# CPU_GPIO.net
KiCad netlist of a schematic drawn in Altium Designer
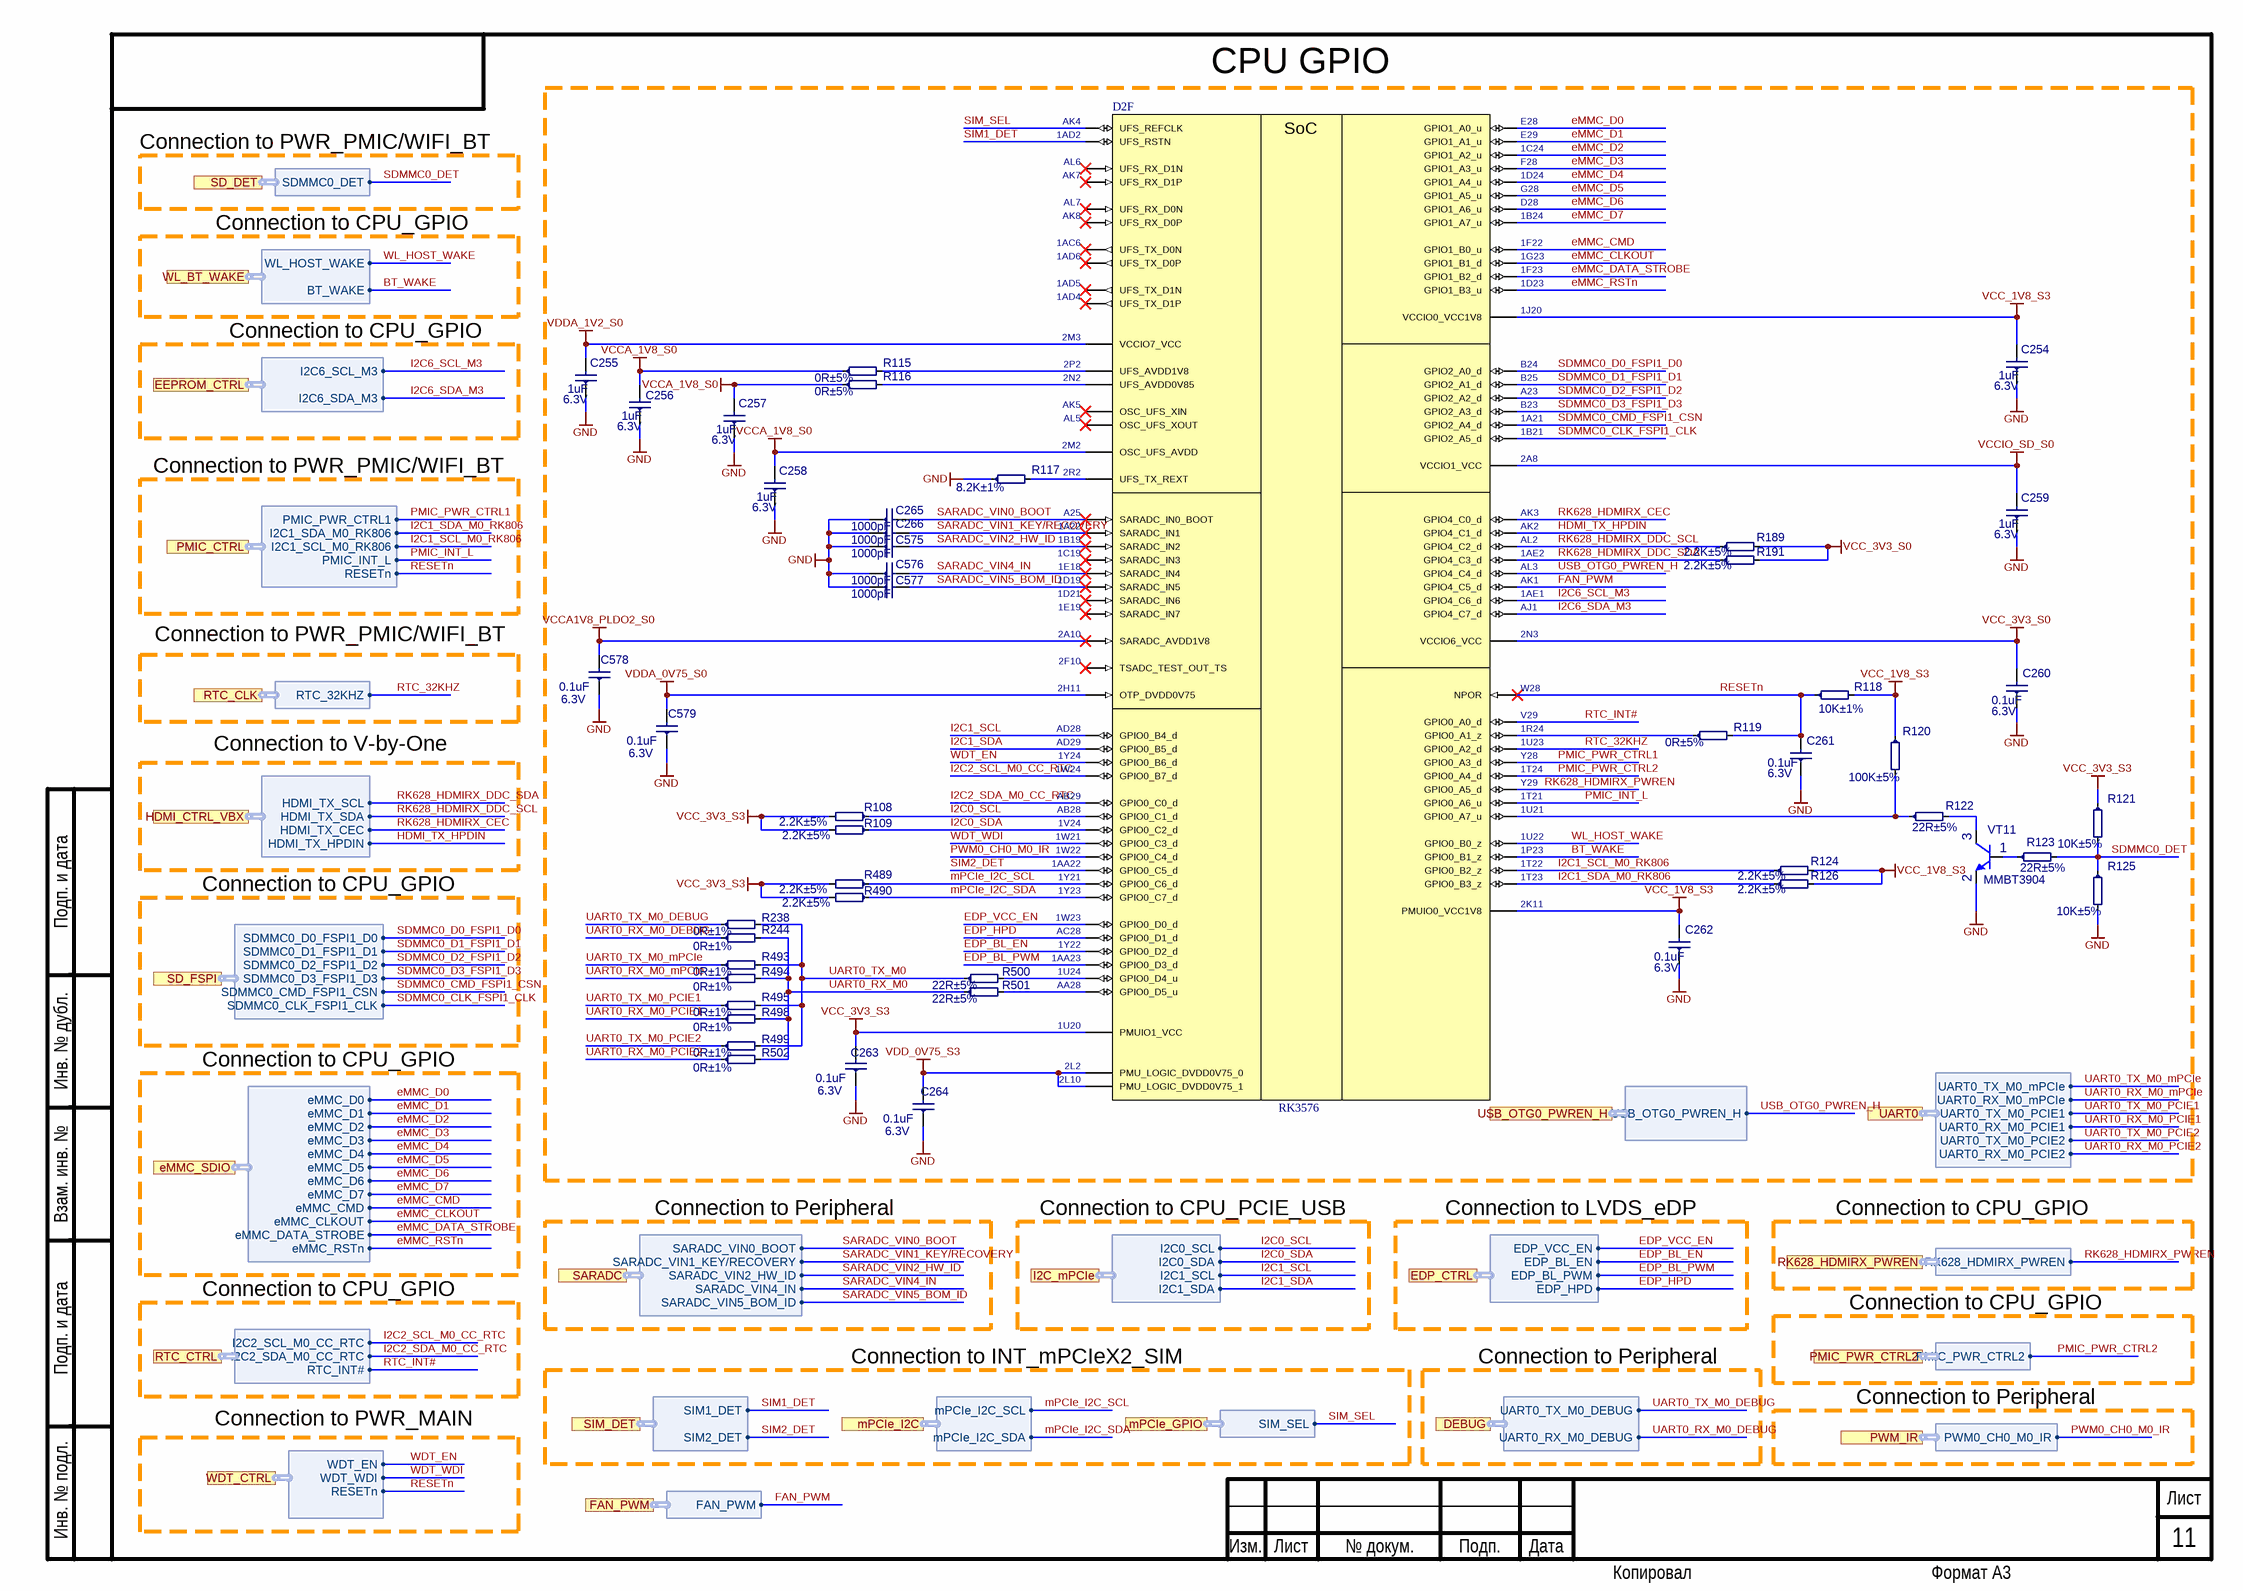
[diagram p0: CPU_GPIO.SchDoc]

(export (version "E")
  (design (tool "Eeschema 10.0.6"))
  (components
    (comp (ref "C254")
      (value "1uF")
      (footprint "C0201")
      (fields
        (field (name "VOLTAGE") "6.3V")
        (field (name "PART NUMBER") "0201-X5R-6.3V-1uF±20%")
        (field (name "TOLERANCE") "20%")
        (field (name "MANUFACTURER") "Murata Electronics")
      )
      (libsource (lib "ATB") (part "C"))
    )
    (comp (ref "C255")
      (value "1uF")
      (footprint "C0201")
      (fields
        (field (name "VOLTAGE") "6.3V")
        (field (name "PART NUMBER") "0201-X5R-6.3V-1uF±20%")
        (field (name "TOLERANCE") "20%")
        (field (name "MANUFACTURER") "Murata Electronics")
      )
      (libsource (lib "ATB") (part "C"))
    )
    (comp (ref "C256")
      (value "1uF")
      (footprint "C0201")
      (fields
        (field (name "VOLTAGE") "6.3V")
        (field (name "PART NUMBER") "0201-X5R-6.3V-1uF±20%")
        (field (name "TOLERANCE") "20%")
        (field (name "MANUFACTURER") "Murata Electronics")
      )
      (libsource (lib "ATB") (part "C"))
    )
    (comp (ref "C257")
      (value "1uF")
      (footprint "C0201")
      (fields
        (field (name "VOLTAGE") "6.3V")
        (field (name "PART NUMBER") "0201-X5R-6.3V-1uF±20%")
        (field (name "TOLERANCE") "20%")
        (field (name "MANUFACTURER") "Murata Electronics")
      )
      (libsource (lib "ATB") (part "C"))
    )
    (comp (ref "C258")
      (value "1uF")
      (footprint "C0201")
      (fields
        (field (name "VOLTAGE") "6.3V")
        (field (name "PART NUMBER") "0201-X5R-6.3V-1uF±20%")
        (field (name "TOLERANCE") "20%")
        (field (name "MANUFACTURER") "Murata Electronics")
      )
      (libsource (lib "ATB") (part "C"))
    )
    (comp (ref "C259")
      (value "1uF")
      (footprint "C0201")
      (fields
        (field (name "VOLTAGE") "6.3V")
        (field (name "PART NUMBER") "0201-X5R-6.3V-1uF±20%")
        (field (name "TOLERANCE") "20%")
        (field (name "MANUFACTURER") "Murata Electronics")
      )
      (libsource (lib "ATB") (part "C"))
    )
    (comp (ref "C260")
      (value "0.1uF")
      (footprint "C0201")
      (fields
        (field (name "VOLTAGE") "6.3V")
        (field (name "PART NUMBER") "0201-X5R-6.3V-0.1uF±10%")
        (field (name "TOLERANCE") "10%")
        (field (name "MANUFACTURER") "Yageo")
      )
      (libsource (lib "ATB") (part "C"))
    )
    (comp (ref "C261")
      (value "0.1uF")
      (footprint "C0201")
      (fields
        (field (name "VOLTAGE") "6.3V")
        (field (name "PART NUMBER") "0201-X5R-6.3V-0.1uF±10%")
        (field (name "TOLERANCE") "10%")
        (field (name "MANUFACTURER") "Yageo")
      )
      (libsource (lib "ATB") (part "C"))
    )
    (comp (ref "C262")
      (value "0.1uF")
      (footprint "C0201")
      (fields
        (field (name "VOLTAGE") "6.3V")
        (field (name "PART NUMBER") "0201-X5R-6.3V-0.1uF±10%")
        (field (name "TOLERANCE") "10%")
        (field (name "MANUFACTURER") "Yageo")
      )
      (libsource (lib "ATB") (part "C"))
    )
    (comp (ref "C263")
      (value "0.1uF")
      (footprint "C0201")
      (fields
        (field (name "VOLTAGE") "6.3V")
        (field (name "PART NUMBER") "0201-X5R-6.3V-0.1uF±10%")
        (field (name "TOLERANCE") "10%")
        (field (name "MANUFACTURER") "Yageo")
      )
      (libsource (lib "ATB") (part "C"))
    )
    (comp (ref "C264")
      (value "0.1uF")
      (footprint "C0201")
      (fields
        (field (name "VOLTAGE") "6.3V")
        (field (name "PART NUMBER") "0201-X5R-6.3V-0.1uF±10%")
        (field (name "TOLERANCE") "10%")
        (field (name "MANUFACTURER") "Yageo")
      )
      (libsource (lib "ATB") (part "C"))
    )
    (comp (ref "C265")
      (value "1000pF")
      (footprint "C0201")
      (fields
        (field (name "VOLTAGE") "25V")
        (field (name "PART NUMBER") "0201-C0G-25V-1000pF±10%")
        (field (name "TOLERANCE") "10%")
      )
      (libsource (lib "ATB") (part "C"))
    )
    (comp (ref "C266")
      (value "1000pF")
      (footprint "C0201")
      (fields
        (field (name "VOLTAGE") "25V")
        (field (name "PART NUMBER") "0201-C0G-25V-1000pF±10%")
        (field (name "TOLERANCE") "10%")
      )
      (libsource (lib "ATB") (part "C"))
    )
    (comp (ref "C575")
      (value "1000pF")
      (footprint "C0201")
      (fields
        (field (name "VOLTAGE") "25V")
        (field (name "PART NUMBER") "0201-C0G-25V-1000pF±10%")
        (field (name "TOLERANCE") "10%")
      )
      (libsource (lib "ATB") (part "C"))
    )
    (comp (ref "C576")
      (value "1000pF")
      (footprint "C0201")
      (fields
        (field (name "VOLTAGE") "25V")
        (field (name "PART NUMBER") "0201-C0G-25V-1000pF±10%")
        (field (name "TOLERANCE") "10%")
      )
      (libsource (lib "ATB") (part "C"))
    )
    (comp (ref "C577")
      (value "1000pF")
      (footprint "C0201")
      (fields
        (field (name "VOLTAGE") "25V")
        (field (name "PART NUMBER") "0201-C0G-25V-1000pF±10%")
        (field (name "TOLERANCE") "10%")
      )
      (libsource (lib "ATB") (part "C"))
    )
    (comp (ref "C578")
      (value "0.1uF")
      (footprint "C0201")
      (fields
        (field (name "VOLTAGE") "6.3V")
        (field (name "PART NUMBER") "0201-X5R-6.3V-0.1uF±10%")
        (field (name "TOLERANCE") "10%")
        (field (name "MANUFACTURER") "Yageo")
      )
      (libsource (lib "ATB") (part "C"))
    )
    (comp (ref "C579")
      (value "0.1uF")
      (footprint "C0201")
      (fields
        (field (name "VOLTAGE") "6.3V")
        (field (name "PART NUMBER") "0201-X5R-6.3V-0.1uF±10%")
        (field (name "TOLERANCE") "10%")
        (field (name "MANUFACTURER") "Yageo")
      )
      (libsource (lib "ATB") (part "C"))
    )
    (comp (ref "D2")
      (value "RK3576")
      (footprint "BGAFCCSP698L")
      (description "SoC 4xCortex-A72@2.2Ghz+4xCortex-A53@2Ghz, LPDDR4/4X/5/5X, SDIO/eMMC/UFS/FSPI, BGA 16.1x17.2x1.0mm")
      (fields (field (name "MANUFACTURER") "Rockship"))
      (libsource (lib "ATB") (part "RK3576"))
    )
    (comp (ref "R108")
      (value "2.2K±5%")
      (footprint "R0402")
      (fields
        (field (name "PART NUMBER") "0402-0.0625W-2.2K-100ppm±5%")
        (field (name "TOLERANCE") "5%")
        (field (name "MANUFACTURER") "Yageo")
      )
      (libsource (lib "ATB") (part "R"))
    )
    (comp (ref "R109")
      (value "2.2K±5%")
      (footprint "R0402")
      (fields
        (field (name "PART NUMBER") "0402-0.0625W-2.2K-100ppm±5%")
        (field (name "TOLERANCE") "5%")
        (field (name "MANUFACTURER") "Yageo")
      )
      (libsource (lib "ATB") (part "R"))
    )
    (comp (ref "R115")
      (value "0R±5%")
      (footprint "R0201")
      (fields
        (field (name "PART NUMBER") "0201-0.05W-0R-100ppm-5%")
        (field (name "TOLERANCE") "5%")
        (field (name "MANUFACTURER") "Yageo")
      )
      (libsource (lib "ATB") (part "R"))
    )
    (comp (ref "R116")
      (value "0R±5%")
      (footprint "R0201")
      (fields
        (field (name "PART NUMBER") "0201-0.05W-0R-100ppm-5%")
        (field (name "TOLERANCE") "5%")
        (field (name "MANUFACTURER") "Yageo")
      )
      (libsource (lib "ATB") (part "R"))
    )
    (comp (ref "R117")
      (value "8.2K±1%")
      (footprint "R0402")
      (fields
        (field (name "PART NUMBER") "0402-0.0625W-8.2K-100ppm±1%")
        (field (name "TOLERANCE") "1%")
        (field (name "MANUFACTURER") "Yageo")
      )
      (libsource (lib "ATB") (part "R"))
    )
    (comp (ref "R118")
      (value "10K±1%")
      (footprint "R0201")
      (fields
        (field (name "PART NUMBER") "0201-0.05W-10K-200ppm-1%")
        (field (name "TOLERANCE") "1%")
        (field (name "MANUFACTURER") "Yageo")
      )
      (libsource (lib "ATB") (part "R"))
    )
    (comp (ref "R119")
      (value "0R±5%")
      (footprint "R0201")
      (fields
        (field (name "PART NUMBER") "0201-0.05W-0R-100ppm-5%")
        (field (name "TOLERANCE") "5%")
        (field (name "MANUFACTURER") "Yageo")
      )
      (libsource (lib "ATB") (part "R"))
    )
    (comp (ref "R120")
      (value "100K±5%")
      (footprint "R0402")
      (fields
        (field (name "PART NUMBER") "0402-0.0625W-100K-100ppm±5%")
        (field (name "TOLERANCE") "5%")
        (field (name "MANUFACTURER") "Yageo")
      )
      (libsource (lib "ATB") (part "R"))
    )
    (comp (ref "R121")
      (value "10K±5%")
      (footprint "R0402")
      (fields
        (field (name "PART NUMBER") "0402-0.0625W-10K-100ppm±5%")
        (field (name "TOLERANCE") "5%")
        (field (name "MANUFACTURER") "Yageo")
      )
      (libsource (lib "ATB") (part "R"))
    )
    (comp (ref "R122")
      (value "22R±5%")
      (footprint "R0402")
      (fields
        (field (name "PART NUMBER") "0402-0.0625W-22R-100ppm±5%")
        (field (name "TOLERANCE") "5%")
        (field (name "MANUFACTURER") "Yageo")
      )
      (libsource (lib "ATB") (part "R"))
    )
    (comp (ref "R123")
      (value "22R±5%")
      (footprint "R0402")
      (fields
        (field (name "PART NUMBER") "0402-0.0625W-22R-100ppm±5%")
        (field (name "TOLERANCE") "5%")
        (field (name "MANUFACTURER") "Yageo")
      )
      (libsource (lib "ATB") (part "R"))
    )
    (comp (ref "R124")
      (value "2.2K±5%")
      (footprint "R0402")
      (fields
        (field (name "PART NUMBER") "0402-0.0625W-2.2K-100ppm±5%")
        (field (name "TOLERANCE") "5%")
        (field (name "MANUFACTURER") "Yageo")
      )
      (libsource (lib "ATB") (part "R"))
    )
    (comp (ref "R125")
      (value "10K±5%")
      (footprint "R0402")
      (fields
        (field (name "PART NUMBER") "0402-0.0625W-10K-100ppm±5%")
        (field (name "TOLERANCE") "5%")
        (field (name "MANUFACTURER") "Yageo")
      )
      (libsource (lib "ATB") (part "R"))
    )
    (comp (ref "R126")
      (value "2.2K±5%")
      (footprint "R0402")
      (fields
        (field (name "PART NUMBER") "0402-0.0625W-2.2K-100ppm±5%")
        (field (name "TOLERANCE") "5%")
        (field (name "MANUFACTURER") "Yageo")
      )
      (libsource (lib "ATB") (part "R"))
    )
    (comp (ref "R189")
      (value "2.2K±5%")
      (footprint "R0402")
      (fields
        (field (name "PART NUMBER") "0402-0.0625W-2.2K-100ppm±5%")
        (field (name "TOLERANCE") "5%")
        (field (name "MANUFACTURER") "Yageo")
      )
      (libsource (lib "ATB") (part "R"))
    )
    (comp (ref "R191")
      (value "2.2K±5%")
      (footprint "R0402")
      (fields
        (field (name "PART NUMBER") "0402-0.0625W-2.2K-100ppm±5%")
        (field (name "TOLERANCE") "5%")
        (field (name "MANUFACTURER") "Yageo")
      )
      (libsource (lib "ATB") (part "R"))
    )
    (comp (ref "R238")
      (value "0R±1%")
      (footprint "R0402")
      (description "Chip Resistor 0402 0Ω ±1% 50V ±100ppm/℃ Thick Film")
      (fields (field (name "PART NUMBER") "0402-0.0625W-0R-100ppm±1%") (field (name "TOLERANCE") "1%"))
      (libsource (lib "ATB") (part "R"))
    )
    (comp (ref "R244")
      (value "0R±1%")
      (footprint "R0402")
      (description "Chip Resistor 0402 0Ω ±1% 50V ±100ppm/℃ Thick Film")
      (fields (field (name "PART NUMBER") "0402-0.0625W-0R-100ppm±1%") (field (name "TOLERANCE") "1%"))
      (libsource (lib "ATB") (part "R"))
    )
    (comp (ref "R489")
      (value "2.2K±5%")
      (footprint "R0402")
      (fields
        (field (name "PART NUMBER") "0402-0.0625W-2.2K-100ppm±5%")
        (field (name "TOLERANCE") "5%")
        (field (name "MANUFACTURER") "Yageo")
      )
      (libsource (lib "ATB") (part "R"))
    )
    (comp (ref "R490")
      (value "2.2K±5%")
      (footprint "R0402")
      (fields
        (field (name "PART NUMBER") "0402-0.0625W-2.2K-100ppm±5%")
        (field (name "TOLERANCE") "5%")
        (field (name "MANUFACTURER") "Yageo")
      )
      (libsource (lib "ATB") (part "R"))
    )
    (comp (ref "R493")
      (value "0R±1%")
      (footprint "R0402")
      (description "Chip Resistor 0402 0Ω ±1% 50V ±100ppm/℃ Thick Film")
      (fields (field (name "PART NUMBER") "0402-0.0625W-0R-100ppm±1%") (field (name "TOLERANCE") "1%"))
      (libsource (lib "ATB") (part "R"))
    )
    (comp (ref "R494")
      (value "0R±1%")
      (footprint "R0402")
      (description "Chip Resistor 0402 0Ω ±1% 50V ±100ppm/℃ Thick Film")
      (fields (field (name "PART NUMBER") "0402-0.0625W-0R-100ppm±1%") (field (name "TOLERANCE") "1%"))
      (libsource (lib "ATB") (part "R"))
    )
    (comp (ref "R495")
      (value "0R±1%")
      (footprint "R0402")
      (description "Chip Resistor 0402 0Ω ±1% 50V ±100ppm/℃ Thick Film")
      (fields (field (name "PART NUMBER") "0402-0.0625W-0R-100ppm±1%") (field (name "TOLERANCE") "1%"))
      (libsource (lib "ATB") (part "R"))
    )
    (comp (ref "R498")
      (value "0R±1%")
      (footprint "R0402")
      (description "Chip Resistor 0402 0Ω ±1% 50V ±100ppm/℃ Thick Film")
      (fields (field (name "PART NUMBER") "0402-0.0625W-0R-100ppm±1%") (field (name "TOLERANCE") "1%"))
      (libsource (lib "ATB") (part "R"))
    )
    (comp (ref "R499")
      (value "0R±1%")
      (footprint "R0402")
      (description "Chip Resistor 0402 0Ω ±1% 50V ±100ppm/℃ Thick Film")
      (fields (field (name "PART NUMBER") "0402-0.0625W-0R-100ppm±1%") (field (name "TOLERANCE") "1%"))
      (libsource (lib "ATB") (part "R"))
    )
    (comp (ref "R500")
      (value "22R±5%")
      (footprint "R0402")
      (fields
        (field (name "PART NUMBER") "0402-0.0625W-22R-100ppm±5%")
        (field (name "TOLERANCE") "5%")
        (field (name "MANUFACTURER") "Yageo")
      )
      (libsource (lib "ATB") (part "R"))
    )
    (comp (ref "R501")
      (value "22R±5%")
      (footprint "R0402")
      (fields
        (field (name "PART NUMBER") "0402-0.0625W-22R-100ppm±5%")
        (field (name "TOLERANCE") "5%")
        (field (name "MANUFACTURER") "Yageo")
      )
      (libsource (lib "ATB") (part "R"))
    )
    (comp (ref "R502")
      (value "0R±1%")
      (footprint "R0402")
      (description "Chip Resistor 0402 0Ω ±1% 50V ±100ppm/℃ Thick Film")
      (fields (field (name "PART NUMBER") "0402-0.0625W-0R-100ppm±1%") (field (name "TOLERANCE") "1%"))
      (libsource (lib "ATB") (part "R"))
    )
    (comp (ref "VT11")
      (value "MMBT3904")
      (footprint "SOT23")
      (description "NPN transistor")
      (fields (field (name "VOLTAGE") "40V") (field (name "MANUFACTURER") "Diotec Semiconductor"))
      (libsource (lib "ATB") (part "BC846BLT1G"))
    )
  )
  (nets
    (net (code "20") (name "/BT_WAKE") (class "Default")
      (node (ref "D2") (pin "1P23") (pinfunction "GPIO0_B1_z_1P23") (pintype "bidirectional"))
    )
    (net (code "21") (name "/EDP_BL_EN") (class "Default")
      (node (ref "D2") (pin "1Y22") (pinfunction "GPIO0_D2_d_1Y22") (pintype "bidirectional"))
    )
    (net (code "22") (name "/EDP_BL_PWM") (class "Default")
      (node (ref "D2") (pin "1AA23") (pinfunction "GPIO0_D3_d_1AA23") (pintype "bidirectional"))
    )
    (net (code "23") (name "/EDP_HPD") (class "Default")
      (node (ref "D2") (pin "AC28") (pinfunction "GPIO0_D1_d_AC28") (pintype "bidirectional"))
    )
    (net (code "24") (name "/EDP_VCC_EN") (class "Default")
      (node (ref "D2") (pin "1W23") (pinfunction "GPIO0_D0_d_1W23") (pintype "bidirectional"))
    )
    (net (code "25") (name "/FAN_PWM") (class "Default")
      (node (ref "D2") (pin "AK1") (pinfunction "GPIO4_C5_d_AK1") (pintype "bidirectional"))
    )
    (net (code "26") (name "/HDMI_TX_HPDIN") (class "Default")
      (node (ref "D2") (pin "AK2") (pinfunction "GPIO4_C1_d_AK2") (pintype "bidirectional"))
    )
    (net (code "27") (name "/I2C0_SCL") (class "Default")
      (node (ref "D2") (pin "AB28") (pinfunction "GPIO0_C1_d_AB28") (pintype "bidirectional"))
      (node (ref "R108") (pin "1") (pinfunction "1_1") (pintype "passive"))
    )
    (net (code "28") (name "/I2C0_SDA") (class "Default")
      (node (ref "D2") (pin "1V24") (pinfunction "GPIO0_C2_d_1V24") (pintype "bidirectional"))
      (node (ref "R109") (pin "1") (pinfunction "1_1") (pintype "passive"))
    )
    (net (code "29") (name "/I2C1_SCL") (class "Default")
      (node (ref "D2") (pin "AD28") (pinfunction "GPIO0_B4_d_AD28") (pintype "bidirectional"))
    )
    (net (code "30") (name "/I2C1_SCL_M0_RK806") (class "Default")
      (node (ref "D2") (pin "1T22") (pinfunction "GPIO0_B2_z_1T22") (pintype "bidirectional"))
      (node (ref "R124") (pin "1") (pinfunction "1_1") (pintype "passive"))
    )
    (net (code "31") (name "/I2C1_SDA") (class "Default")
      (node (ref "D2") (pin "AD29") (pinfunction "GPIO0_B5_d_AD29") (pintype "bidirectional"))
    )
    (net (code "32") (name "/I2C1_SDA_M0_RK806") (class "Default")
      (node (ref "D2") (pin "1T23") (pinfunction "GPIO0_B3_z_1T23") (pintype "bidirectional"))
      (node (ref "R126") (pin "1") (pinfunction "1_1") (pintype "passive"))
    )
    (net (code "33") (name "/I2C2_SCL_M0_CC_RTC") (class "Default")
      (node (ref "D2") (pin "1W24") (pinfunction "GPIO0_B7_d_1W24") (pintype "bidirectional"))
    )
    (net (code "34") (name "/I2C2_SDA_M0_CC_RTC") (class "Default")
      (node (ref "D2") (pin "AB29") (pinfunction "GPIO0_C0_d_AB29") (pintype "bidirectional"))
    )
    (net (code "35") (name "/I2C6_SCL_M3") (class "Default")
      (node (ref "D2") (pin "1AE1") (pinfunction "GPIO4_C6_d_1AE1") (pintype "bidirectional"))
    )
    (net (code "36") (name "/I2C6_SDA_M3") (class "Default")
      (node (ref "D2") (pin "AJ1") (pinfunction "GPIO4_C7_d_AJ1") (pintype "bidirectional"))
    )
    (net (code "37") (name "/PMIC_INT_L") (class "Default")
      (node (ref "D2") (pin "1T21") (pinfunction "GPIO0_A6_u_1T21") (pintype "bidirectional"))
    )
    (net (code "38") (name "/PMIC_PWR_CTRL1") (class "Default")
      (node (ref "D2") (pin "Y28") (pinfunction "GPIO0_A3_d_Y28") (pintype "bidirectional"))
    )
    (net (code "39") (name "/PMIC_PWR_CTRL2") (class "Default")
      (node (ref "D2") (pin "1T24") (pinfunction "GPIO0_A4_d_1T24") (pintype "bidirectional"))
    )
    (net (code "40") (name "/PWM0_CH0_M0_IR") (class "Default")
      (node (ref "D2") (pin "1W22") (pinfunction "GPIO0_C4_d_1W22") (pintype "bidirectional"))
    )
    (net (code "41") (name "/RESETn") (class "Default")
      (node (ref "C261") (pin "2") (pinfunction "2_2") (pintype "passive"))
      (node (ref "D2") (pin "W28") (pinfunction "NPOR_W28") (pintype "input"))
      (node (ref "R118") (pin "1") (pinfunction "1_1") (pintype "passive"))
      (node (ref "R119") (pin "2") (pinfunction "2_2") (pintype "passive"))
    )
    (net (code "42") (name "/RK628_HDMIRX_CEC") (class "Default")
      (node (ref "D2") (pin "AK3") (pinfunction "GPIO4_C0_d_AK3") (pintype "bidirectional"))
    )
    (net (code "43") (name "/RK628_HDMIRX_DDC_SCL") (class "Default")
      (node (ref "D2") (pin "AL2") (pinfunction "GPIO4_C2_d_AL2") (pintype "bidirectional"))
      (node (ref "R189") (pin "1") (pinfunction "1_1") (pintype "passive"))
    )
    (net (code "44") (name "/RK628_HDMIRX_DDC_SDA") (class "Default")
      (node (ref "D2") (pin "1AE2") (pinfunction "GPIO4_C3_d_1AE2") (pintype "bidirectional"))
      (node (ref "R191") (pin "1") (pinfunction "1_1") (pintype "passive"))
    )
    (net (code "45") (name "/RK628_HDMIRX_PWREN") (class "Default")
      (node (ref "D2") (pin "Y29") (pinfunction "GPIO0_A5_d_Y29") (pintype "bidirectional"))
    )
    (net (code "46") (name "/RTC_32KHZ") (class "Default")
      (node (ref "D2") (pin "1U23") (pinfunction "GPIO0_A2_d_1U23") (pintype "bidirectional"))
    )
    (net (code "47") (name "/RTC_INT#") (class "Default")
      (node (ref "D2") (pin "V29") (pinfunction "GPIO0_A0_d_V29") (pintype "bidirectional"))
    )
    (net (code "48") (name "/SARADC_VIN0_BOOT") (class "Default")
      (node (ref "C265") (pin "2") (pinfunction "2_2") (pintype "passive"))
      (node (ref "D2") (pin "A25") (pinfunction "SARADC_IN0_BOOT_A25") (pintype "input"))
    )
    (net (code "49") (name "/SARADC_VIN1_KEY{slash}RECOVERY") (class "Default")
      (node (ref "C266") (pin "2") (pinfunction "2_2") (pintype "passive"))
      (node (ref "D2") (pin "1A22") (pinfunction "SARADC_IN1_1A22") (pintype "input"))
    )
    (net (code "50") (name "/SARADC_VIN2_HW_ID") (class "Default")
      (node (ref "C575") (pin "2") (pinfunction "2_2") (pintype "passive"))
      (node (ref "D2") (pin "1B19") (pinfunction "SARADC_IN2_1B19") (pintype "input"))
    )
    (net (code "51") (name "/SARADC_VIN4_IN") (class "Default")
      (node (ref "C576") (pin "2") (pinfunction "2_2") (pintype "passive"))
      (node (ref "D2") (pin "1E18") (pinfunction "SARADC_IN4_1E18") (pintype "input"))
    )
    (net (code "52") (name "/SARADC_VIN5_BOM_ID") (class "Default")
      (node (ref "C577") (pin "2") (pinfunction "2_2") (pintype "passive"))
      (node (ref "D2") (pin "1D19") (pinfunction "SARADC_IN5_1D19") (pintype "input"))
    )
    (net (code "53") (name "/SDMMC0_CLK_FSPI1_CLK") (class "Default")
      (node (ref "D2") (pin "1B21") (pinfunction "GPIO2_A5_d_1B21") (pintype "bidirectional"))
    )
    (net (code "54") (name "/SDMMC0_CMD_FSPI1_CSN") (class "Default")
      (node (ref "D2") (pin "1A21") (pinfunction "GPIO2_A4_d_1A21") (pintype "bidirectional"))
    )
    (net (code "55") (name "/SDMMC0_D0_FSPI1_D0") (class "Default")
      (node (ref "D2") (pin "B24") (pinfunction "GPIO2_A0_d_B24") (pintype "bidirectional"))
    )
    (net (code "56") (name "/SDMMC0_D1_FSPI1_D1") (class "Default")
      (node (ref "D2") (pin "B25") (pinfunction "GPIO2_A1_d_B25") (pintype "bidirectional"))
    )
    (net (code "57") (name "/SDMMC0_D2_FSPI1_D2") (class "Default")
      (node (ref "D2") (pin "A23") (pinfunction "GPIO2_A2_d_A23") (pintype "bidirectional"))
    )
    (net (code "58") (name "/SDMMC0_D3_FSPI1_D3") (class "Default")
      (node (ref "D2") (pin "B23") (pinfunction "GPIO2_A3_d_B23") (pintype "bidirectional"))
    )
    (net (code "59") (name "/SDMMC0_DET") (class "Default")
      (node (ref "R121") (pin "2") (pinfunction "2_2") (pintype "passive"))
      (node (ref "R123") (pin "2") (pinfunction "2_2") (pintype "passive"))
      (node (ref "R125") (pin "1") (pinfunction "1_1") (pintype "passive"))
    )
    (net (code "60") (name "/SIM1_DET") (class "Default")
      (node (ref "D2") (pin "1AD2") (pinfunction "UFS_RSTN_1AD2") (pintype "bidirectional"))
    )
    (net (code "61") (name "/SIM2_DET") (class "Default")
      (node (ref "D2") (pin "1AA22") (pinfunction "GPIO0_C5_d_1AA22") (pintype "bidirectional"))
    )
    (net (code "62") (name "/SIM_SEL") (class "Default")
      (node (ref "D2") (pin "AK4") (pinfunction "UFS_REFCLK_AK4") (pintype "bidirectional"))
    )
    (net (code "63") (name "/UART0_RX_M0") (class "Default")
      (node (ref "R244") (pin "2") (pinfunction "2_2") (pintype "passive"))
      (node (ref "R494") (pin "2") (pinfunction "2_2") (pintype "passive"))
      (node (ref "R498") (pin "2") (pinfunction "2_2") (pintype "passive"))
      (node (ref "R501") (pin "1") (pinfunction "1_1") (pintype "passive"))
      (node (ref "R502") (pin "2") (pinfunction "2_2") (pintype "passive"))
    )
    (net (code "64") (name "/UART0_RX_M0_DEBUG") (class "Default")
      (node (ref "R244") (pin "1") (pinfunction "1_1") (pintype "passive"))
    )
    (net (code "65") (name "/UART0_RX_M0_PCIE1") (class "Default")
      (node (ref "R498") (pin "1") (pinfunction "1_1") (pintype "passive"))
    )
    (net (code "66") (name "/UART0_RX_M0_PCIE2") (class "Default")
      (node (ref "R502") (pin "1") (pinfunction "1_1") (pintype "passive"))
    )
    (net (code "67") (name "/UART0_RX_M0_mPCIe") (class "Default")
      (node (ref "R494") (pin "1") (pinfunction "1_1") (pintype "passive"))
    )
    (net (code "68") (name "/UART0_TX_M0") (class "Default")
      (node (ref "R238") (pin "2") (pinfunction "2_2") (pintype "passive"))
      (node (ref "R493") (pin "2") (pinfunction "2_2") (pintype "passive"))
      (node (ref "R495") (pin "2") (pinfunction "2_2") (pintype "passive"))
      (node (ref "R499") (pin "2") (pinfunction "2_2") (pintype "passive"))
      (node (ref "R500") (pin "1") (pinfunction "1_1") (pintype "passive"))
    )
    (net (code "69") (name "/UART0_TX_M0_DEBUG") (class "Default")
      (node (ref "R238") (pin "1") (pinfunction "1_1") (pintype "passive"))
    )
    (net (code "70") (name "/UART0_TX_M0_PCIE1") (class "Default")
      (node (ref "R495") (pin "1") (pinfunction "1_1") (pintype "passive"))
    )
    (net (code "71") (name "/UART0_TX_M0_PCIE2") (class "Default")
      (node (ref "R499") (pin "1") (pinfunction "1_1") (pintype "passive"))
    )
    (net (code "72") (name "/UART0_TX_M0_mPCIe") (class "Default")
      (node (ref "R493") (pin "1") (pinfunction "1_1") (pintype "passive"))
    )
    (net (code "73") (name "/USB_OTG0_PWREN_H") (class "Default")
      (node (ref "D2") (pin "AL3") (pinfunction "GPIO4_C4_d_AL3") (pintype "bidirectional"))
    )
    (net (code "74") (name "/WDT_EN") (class "Default")
      (node (ref "D2") (pin "1Y24") (pinfunction "GPIO0_B6_d_1Y24") (pintype "bidirectional"))
    )
    (net (code "75") (name "/WDT_WDI") (class "Default")
      (node (ref "D2") (pin "1W21") (pinfunction "GPIO0_C3_d_1W21") (pintype "bidirectional"))
    )
    (net (code "76") (name "/WL_HOST_WAKE") (class "Default")
      (node (ref "D2") (pin "1U22") (pinfunction "GPIO0_B0_z_1U22") (pintype "bidirectional"))
    )
    (net (code "77") (name "/eMMC_CLKOUT") (class "Default")
      (node (ref "D2") (pin "1G23") (pinfunction "GPIO1_B1_d_1G23") (pintype "bidirectional"))
    )
    (net (code "78") (name "/eMMC_CMD") (class "Default")
      (node (ref "D2") (pin "1F22") (pinfunction "GPIO1_B0_u_1F22") (pintype "bidirectional"))
    )
    (net (code "79") (name "/eMMC_D0") (class "Default")
      (node (ref "D2") (pin "E28") (pinfunction "GPIO1_A0_u_E28") (pintype "bidirectional"))
    )
    (net (code "80") (name "/eMMC_D1") (class "Default")
      (node (ref "D2") (pin "E29") (pinfunction "GPIO1_A1_u_E29") (pintype "bidirectional"))
    )
    (net (code "81") (name "/eMMC_D2") (class "Default")
      (node (ref "D2") (pin "1C24") (pinfunction "GPIO1_A2_u_1C24") (pintype "bidirectional"))
    )
    (net (code "82") (name "/eMMC_D3") (class "Default")
      (node (ref "D2") (pin "F28") (pinfunction "GPIO1_A3_u_F28") (pintype "bidirectional"))
    )
    (net (code "83") (name "/eMMC_D4") (class "Default")
      (node (ref "D2") (pin "1D24") (pinfunction "GPIO1_A4_u_1D24") (pintype "bidirectional"))
    )
    (net (code "84") (name "/eMMC_D5") (class "Default")
      (node (ref "D2") (pin "G28") (pinfunction "GPIO1_A5_u_G28") (pintype "bidirectional"))
    )
    (net (code "85") (name "/eMMC_D6") (class "Default")
      (node (ref "D2") (pin "D28") (pinfunction "GPIO1_A6_u_D28") (pintype "bidirectional"))
    )
    (net (code "86") (name "/eMMC_D7") (class "Default")
      (node (ref "D2") (pin "1B24") (pinfunction "GPIO1_A7_u_1B24") (pintype "bidirectional"))
    )
    (net (code "87") (name "/eMMC_DATA_STROBE") (class "Default")
      (node (ref "D2") (pin "1F23") (pinfunction "GPIO1_B2_d_1F23") (pintype "bidirectional"))
    )
    (net (code "88") (name "/eMMC_RSTn") (class "Default")
      (node (ref "D2") (pin "1D23") (pinfunction "GPIO1_B3_u_1D23") (pintype "bidirectional"))
    )
    (net (code "89") (name "/mPCIe_I2C_SCL") (class "Default")
      (node (ref "D2") (pin "1Y21") (pinfunction "GPIO0_C6_d_1Y21") (pintype "bidirectional"))
      (node (ref "R489") (pin "1") (pinfunction "1_1") (pintype "passive"))
    )
    (net (code "90") (name "/mPCIe_I2C_SDA") (class "Default")
      (node (ref "D2") (pin "1Y23") (pinfunction "GPIO0_C7_d_1Y23") (pintype "bidirectional"))
      (node (ref "R490") (pin "1") (pinfunction "1_1") (pintype "passive"))
    )
    (net (code "114") (name "GND") (class "Default")
      (node (ref "C254") (pin "1") (pinfunction "1_1") (pintype "passive"))
      (node (ref "C255") (pin "1") (pinfunction "1_1") (pintype "passive"))
      (node (ref "C256") (pin "1") (pinfunction "1_1") (pintype "passive"))
      (node (ref "C257") (pin "1") (pinfunction "1_1") (pintype "passive"))
      (node (ref "C258") (pin "1") (pinfunction "1_1") (pintype "passive"))
      (node (ref "C259") (pin "1") (pinfunction "1_1") (pintype "passive"))
      (node (ref "C260") (pin "1") (pinfunction "1_1") (pintype "passive"))
      (node (ref "C261") (pin "1") (pinfunction "1_1") (pintype "passive"))
      (node (ref "C262") (pin "1") (pinfunction "1_1") (pintype "passive"))
      (node (ref "C263") (pin "1") (pinfunction "1_1") (pintype "passive"))
      (node (ref "C264") (pin "1") (pinfunction "1_1") (pintype "passive"))
      (node (ref "C265") (pin "1") (pinfunction "1_1") (pintype "passive"))
      (node (ref "C266") (pin "1") (pinfunction "1_1") (pintype "passive"))
      (node (ref "C575") (pin "1") (pinfunction "1_1") (pintype "passive"))
      (node (ref "C576") (pin "1") (pinfunction "1_1") (pintype "passive"))
      (node (ref "C577") (pin "1") (pinfunction "1_1") (pintype "passive"))
      (node (ref "C578") (pin "1") (pinfunction "1_1") (pintype "passive"))
      (node (ref "C579") (pin "1") (pinfunction "1_1") (pintype "passive"))
      (node (ref "R117") (pin "1") (pinfunction "1_1") (pintype "passive"))
      (node (ref "R125") (pin "2") (pinfunction "2_2") (pintype "passive"))
      (node (ref "VT11") (pin "2") (pinfunction "E_2") (pintype "passive"))
    )
    (net (code "115") (name "Net-(D2F-GPIO0_A1_z)") (class "Default")
      (node (ref "D2") (pin "1R24") (pinfunction "GPIO0_A1_z_1R24") (pintype "bidirectional"))
      (node (ref "R119") (pin "1") (pinfunction "1_1") (pintype "passive"))
    )
    (net (code "116") (name "Net-(D2F-GPIO0_A7_u)") (class "Default")
      (node (ref "D2") (pin "1U21") (pinfunction "GPIO0_A7_u_1U21") (pintype "bidirectional"))
      (node (ref "R120") (pin "2") (pinfunction "2_2") (pintype "passive"))
      (node (ref "R122") (pin "1") (pinfunction "1_1") (pintype "passive"))
    )
    (net (code "117") (name "Net-(D2F-GPIO0_D4_u)") (class "Default")
      (node (ref "D2") (pin "1U24") (pinfunction "GPIO0_D4_u_1U24") (pintype "bidirectional"))
      (node (ref "R500") (pin "2") (pinfunction "2_2") (pintype "passive"))
    )
    (net (code "118") (name "Net-(D2F-GPIO0_D5_u)") (class "Default")
      (node (ref "D2") (pin "AA28") (pinfunction "GPIO0_D5_u_AA28") (pintype "bidirectional"))
      (node (ref "R501") (pin "2") (pinfunction "2_2") (pintype "passive"))
    )
    (net (code "119") (name "Net-(D2F-UFS_AVDD0V85)") (class "Default")
      (node (ref "D2") (pin "2N2") (pinfunction "UFS_AVDD0V85_2N2") (pintype "power_in"))
      (node (ref "R116") (pin "2") (pinfunction "2_2") (pintype "passive"))
    )
    (net (code "120") (name "Net-(D2F-UFS_AVDD1V8)") (class "Default")
      (node (ref "D2") (pin "2P2") (pinfunction "UFS_AVDD1V8_2P2") (pintype "power_in"))
      (node (ref "R115") (pin "2") (pinfunction "2_2") (pintype "passive"))
    )
    (net (code "121") (name "Net-(D2F-UFS_TX_REXT)") (class "Default")
      (node (ref "D2") (pin "2R2") (pinfunction "UFS_TX_REXT_2R2") (pintype "passive"))
      (node (ref "R117") (pin "2") (pinfunction "2_2") (pintype "passive"))
    )
    (net (code "122") (name "Net-(VT11-B)") (class "Default")
      (node (ref "R123") (pin "1") (pinfunction "1_1") (pintype "passive"))
      (node (ref "VT11") (pin "1") (pinfunction "B_1") (pintype "passive"))
    )
    (net (code "123") (name "Net-(VT11-C)") (class "Default")
      (node (ref "R122") (pin "2") (pinfunction "2_2") (pintype "passive"))
      (node (ref "VT11") (pin "3") (pinfunction "C_3") (pintype "passive"))
    )
    (net (code "124") (name "VCCA1V8_PLDO2_S0") (class "Default")
      (node (ref "C578") (pin "2") (pinfunction "2_2") (pintype "passive"))
      (node (ref "D2") (pin "2A10") (pinfunction "SARADC_AVDD1V8_2A10") (pintype "input"))
    )
    (net (code "125") (name "VCCA_1V8_S0") (class "Default")
      (node (ref "C256") (pin "2") (pinfunction "2_2") (pintype "passive"))
      (node (ref "C257") (pin "2") (pinfunction "2_2") (pintype "passive"))
      (node (ref "C258") (pin "2") (pinfunction "2_2") (pintype "passive"))
      (node (ref "D2") (pin "2M2") (pinfunction "OSC_UFS_AVDD_2M2") (pintype "power_in"))
      (node (ref "R115") (pin "1") (pinfunction "1_1") (pintype "passive"))
      (node (ref "R116") (pin "1") (pinfunction "1_1") (pintype "passive"))
    )
    (net (code "126") (name "VCCIO_SD_S0") (class "Default")
      (node (ref "C259") (pin "2") (pinfunction "2_2") (pintype "passive"))
      (node (ref "D2") (pin "2A8") (pinfunction "VCCIO1_VCC_2A8") (pintype "power_in"))
    )
    (net (code "127") (name "VCC_1V8_S3") (class "Default")
      (node (ref "C254") (pin "2") (pinfunction "2_2") (pintype "passive"))
      (node (ref "C262") (pin "2") (pinfunction "2_2") (pintype "passive"))
      (node (ref "D2") (pin "1J20") (pinfunction "VCCIO0_VCC1V8_1J20") (pintype "power_in"))
      (node (ref "D2") (pin "2K11") (pinfunction "PMUIO0_VCC1V8_2K11") (pintype "power_in"))
      (node (ref "R118") (pin "2") (pinfunction "2_2") (pintype "passive"))
      (node (ref "R120") (pin "1") (pinfunction "1_1") (pintype "passive"))
      (node (ref "R124") (pin "2") (pinfunction "2_2") (pintype "passive"))
      (node (ref "R126") (pin "2") (pinfunction "2_2") (pintype "passive"))
    )
    (net (code "128") (name "VCC_3V3_S0") (class "Default")
      (node (ref "C260") (pin "2") (pinfunction "2_2") (pintype "passive"))
      (node (ref "D2") (pin "2N3") (pinfunction "VCCIO6_VCC_2N3") (pintype "power_in"))
      (node (ref "R189") (pin "2") (pinfunction "2_2") (pintype "passive"))
      (node (ref "R191") (pin "2") (pinfunction "2_2") (pintype "passive"))
    )
    (net (code "129") (name "VCC_3V3_S3") (class "Default")
      (node (ref "C263") (pin "2") (pinfunction "2_2") (pintype "passive"))
      (node (ref "D2") (pin "1U20") (pinfunction "PMUIO1_VCC_1U20") (pintype "power_in"))
      (node (ref "R108") (pin "2") (pinfunction "2_2") (pintype "passive"))
      (node (ref "R109") (pin "2") (pinfunction "2_2") (pintype "passive"))
      (node (ref "R121") (pin "1") (pinfunction "1_1") (pintype "passive"))
      (node (ref "R489") (pin "2") (pinfunction "2_2") (pintype "passive"))
      (node (ref "R490") (pin "2") (pinfunction "2_2") (pintype "passive"))
    )
    (net (code "130") (name "VDDA_0V75_S0") (class "Default")
      (node (ref "C579") (pin "2") (pinfunction "2_2") (pintype "passive"))
      (node (ref "D2") (pin "2H11") (pinfunction "OTP_DVDD0V75_2H11") (pintype "input"))
    )
    (net (code "131") (name "VDDA_1V2_S0") (class "Default")
      (node (ref "C255") (pin "2") (pinfunction "2_2") (pintype "passive"))
      (node (ref "D2") (pin "2M3") (pinfunction "VCCIO7_VCC_2M3") (pintype "power_in"))
    )
    (net (code "132") (name "VDD_0V75_S3") (class "Default")
      (node (ref "C264") (pin "2") (pinfunction "2_2") (pintype "passive"))
      (node (ref "D2") (pin "2L10") (pinfunction "PMU_LOGIC_DVDD0V75_1_2L10") (pintype "power_in"))
      (node (ref "D2") (pin "2L2") (pinfunction "PMU_LOGIC_DVDD0V75_0_2L2") (pintype "power_in"))
    )
    (net (code "133") (name "unconnected-(D2F-OSC_UFS_XIN-PadAK5)") (class "Default")
      (node (ref "D2") (pin "AK5") (pinfunction "OSC_UFS_XIN_AK5") (pintype "passive+no_connect"))
    )
    (net (code "134") (name "unconnected-(D2F-OSC_UFS_XOUT-PadAL5)") (class "Default")
      (node (ref "D2") (pin "AL5") (pinfunction "OSC_UFS_XOUT_AL5") (pintype "passive+no_connect"))
    )
    (net (code "135") (name "unconnected-(D2F-SARADC_IN3-Pad1C19)") (class "Default")
      (node (ref "D2") (pin "1C19") (pinfunction "SARADC_IN3_1C19") (pintype "input+no_connect"))
    )
    (net (code "136") (name "unconnected-(D2F-SARADC_IN6-Pad1D21)") (class "Default")
      (node (ref "D2") (pin "1D21") (pinfunction "SARADC_IN6_1D21") (pintype "input+no_connect"))
    )
    (net (code "137") (name "unconnected-(D2F-SARADC_IN7-Pad1E19)") (class "Default")
      (node (ref "D2") (pin "1E19") (pinfunction "SARADC_IN7_1E19") (pintype "input+no_connect"))
    )
    (net (code "138") (name "unconnected-(D2F-TSADC_TEST_OUT_TS-Pad2F10)") (class "Default")
      (node (ref "D2") (pin "2F10") (pinfunction "TSADC_TEST_OUT_TS_2F10") (pintype "input+no_connect"))
    )
    (net (code "139") (name "unconnected-(D2F-UFS_RX_D0N-PadAL7)") (class "Default")
      (node (ref "D2") (pin "AL7") (pinfunction "UFS_RX_D0N_AL7") (pintype "input+no_connect"))
    )
    (net (code "140") (name "unconnected-(D2F-UFS_RX_D0P-PadAK8)") (class "Default")
      (node (ref "D2") (pin "AK8") (pinfunction "UFS_RX_D0P_AK8") (pintype "input+no_connect"))
    )
    (net (code "141") (name "unconnected-(D2F-UFS_RX_D1N-PadAL6)") (class "Default")
      (node (ref "D2") (pin "AL6") (pinfunction "UFS_RX_D1N_AL6") (pintype "input+no_connect"))
    )
    (net (code "142") (name "unconnected-(D2F-UFS_RX_D1P-PadAK7)") (class "Default")
      (node (ref "D2") (pin "AK7") (pinfunction "UFS_RX_D1P_AK7") (pintype "input+no_connect"))
    )
    (net (code "143") (name "unconnected-(D2F-UFS_TX_D0N-Pad1AC6)") (class "Default")
      (node (ref "D2") (pin "1AC6") (pinfunction "UFS_TX_D0N_1AC6") (pintype "output+no_connect"))
    )
    (net (code "144") (name "unconnected-(D2F-UFS_TX_D0P-Pad1AD6)") (class "Default")
      (node (ref "D2") (pin "1AD6") (pinfunction "UFS_TX_D0P_1AD6") (pintype "output+no_connect"))
    )
    (net (code "145") (name "unconnected-(D2F-UFS_TX_D1N-Pad1AD5)") (class "Default")
      (node (ref "D2") (pin "1AD5") (pinfunction "UFS_TX_D1N_1AD5") (pintype "output+no_connect"))
    )
    (net (code "146") (name "unconnected-(D2F-UFS_TX_D1P-Pad1AD4)") (class "Default")
      (node (ref "D2") (pin "1AD4") (pinfunction "UFS_TX_D1P_1AD4") (pintype "output+no_connect"))
    )
  )
)
